# PHY.net
KiCad netlist of a schematic drawn in Altium Designer
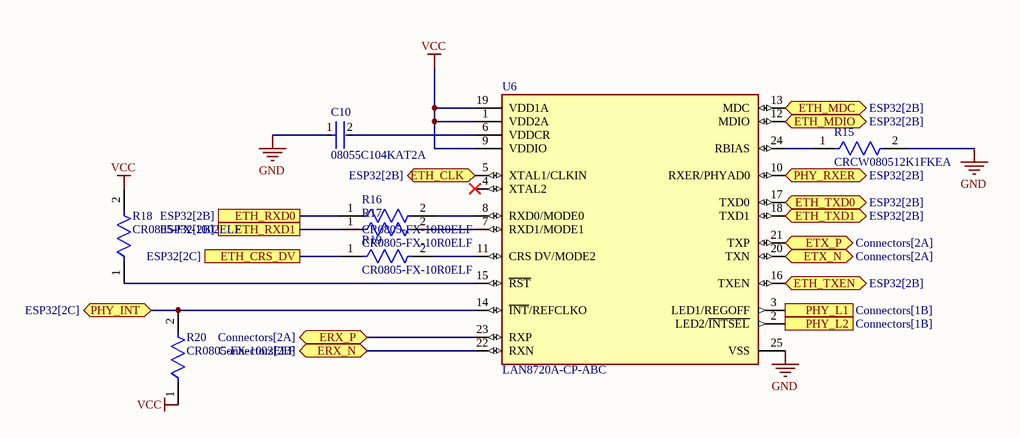
[diagram p0: PHY.SchDoc]

(export (version "E")
  (design (tool "Eeschema 10.0.6"))
  (components
    (comp (ref "C10")
      (value "08055C104KAT2A")
      (footprint "FP-0805-L_2_01_0_2-W_1_25-IPC_C")
      (description "General Purpose Ceramic Capacitor, 0805, 100nF, 10%, X7R, 0.15, 50V")
      (fields (field (name "TOLERANCE") "10%") (field (name "VOLTAGE") "50V"))
      (libsource (lib "Altium Content Vault") (part "02cd4be3c70576c341d710602a673aa"))
    )
    (comp (ref "R15")
      (value "CRCW080512K1FKEA")
      (footprint "FP-CRCW0805-e3-IPC_B")
      (description "RES Thick Film, 12.1kΩ, 1%, 0.125W, 100ppm/°C, 0805")
      (fields (field (name "TOLERANCE") "1%"))
      (libsource (lib "Altium Content Vault") (part "1029c3af85768c4190bb7ad29bc67b5"))
    )
    (comp (ref "R16")
      (value "CR0805-FX-10R0ELF")
      (footprint "FP-CR0805-IPC_B")
      (description "Thick Film Chip Resistors 0805 10Ω 0.125W 1% 100ppm/°C")
      (fields (field (name "TOLERANCE") "1%"))
      (libsource (lib "Altium Content Vault") (part "1029c3af85768c4190bb7ad29bc67b5"))
    )
    (comp (ref "R17")
      (value "CR0805-FX-10R0ELF")
      (footprint "FP-CR0805-IPC_B")
      (description "Thick Film Chip Resistors 0805 10Ω 0.125W 1% 100ppm/°C")
      (fields (field (name "TOLERANCE") "1%"))
      (libsource (lib "Altium Content Vault") (part "1029c3af85768c4190bb7ad29bc67b5"))
    )
    (comp (ref "R18")
      (value "CR0805-FX-1002ELF")
      (footprint "FP-CR0805-IPC_A")
      (description "Thick Film Chip Resistors 0805 10kΩ 0.125W 1% 100ppm/°C")
      (fields (field (name "TOLERANCE") "1%"))
      (libsource (lib "Altium Content Vault") (part "1029c3af85768c4190bb7ad29bc67b5"))
    )
    (comp (ref "R19")
      (value "CR0805-FX-10R0ELF")
      (footprint "FP-CR0805-IPC_B")
      (description "Thick Film Chip Resistors 0805 10Ω 0.125W 1% 100ppm/°C")
      (fields (field (name "TOLERANCE") "1%"))
      (libsource (lib "Altium Content Vault") (part "1029c3af85768c4190bb7ad29bc67b5"))
    )
    (comp (ref "R20")
      (value "CR0805-FX-1002ELF")
      (footprint "FP-CR0805-IPC_A")
      (description "Thick Film Chip Resistors 0805 10kΩ 0.125W 1% 100ppm/°C")
      (fields (field (name "TOLERANCE") "1%"))
      (libsource (lib "Altium Content Vault") (part "1029c3af85768c4190bb7ad29bc67b5"))
    )
    (comp (ref "U6")
      (value "LAN8720A-CP-ABC")
      (footprint "FP-24-S4QFN-4x4B-0_5P-IPC_B")
      (description "IC TRANSCEIVER FULL 2/2 24SQFN")
      (libsource (lib "Altium Content Vault") (part "85d2e6b3fccd3bdbf69e837699e532a"))
    )
  )
  (nets
    (net (code "1") (name "/ERX_N") (class "Default")
      (node (ref "U6") (pin "22") (pinfunction "RXN_22") (pintype "bidirectional"))
    )
    (net (code "2") (name "/ERX_P") (class "Default")
      (node (ref "U6") (pin "23") (pinfunction "RXP_23") (pintype "bidirectional"))
    )
    (net (code "3") (name "/ETH_CLK") (class "Default")
      (node (ref "U6") (pin "5") (pinfunction "XTAL1/CLKIN_5") (pintype "bidirectional"))
    )
    (net (code "4") (name "/ETH_CRS_DV") (class "Default")
      (node (ref "R19") (pin "1") (pinfunction "1_1") (pintype "passive"))
    )
    (net (code "5") (name "/ETH_MDC") (class "Default")
      (node (ref "U6") (pin "13") (pinfunction "MDC_13") (pintype "bidirectional"))
    )
    (net (code "6") (name "/ETH_MDIO") (class "Default")
      (node (ref "U6") (pin "12") (pinfunction "MDIO_12") (pintype "bidirectional"))
    )
    (net (code "7") (name "/ETH_RXD0") (class "Default")
      (node (ref "R16") (pin "1") (pinfunction "1_1") (pintype "passive"))
    )
    (net (code "8") (name "/ETH_RXD1") (class "Default")
      (node (ref "R17") (pin "1") (pinfunction "1_1") (pintype "passive"))
    )
    (net (code "9") (name "/ETH_TXD0") (class "Default")
      (node (ref "U6") (pin "17") (pinfunction "TXD0_17") (pintype "bidirectional"))
    )
    (net (code "10") (name "/ETH_TXD1") (class "Default")
      (node (ref "U6") (pin "18") (pinfunction "TXD1_18") (pintype "bidirectional"))
    )
    (net (code "11") (name "/ETH_TXEN") (class "Default")
      (node (ref "U6") (pin "16") (pinfunction "TXEN_16") (pintype "bidirectional"))
    )
    (net (code "12") (name "/ETX_N") (class "Default")
      (node (ref "U6") (pin "20") (pinfunction "TXN_20") (pintype "bidirectional"))
    )
    (net (code "13") (name "/ETX_P") (class "Default")
      (node (ref "U6") (pin "21") (pinfunction "TXP_21") (pintype "bidirectional"))
    )
    (net (code "14") (name "/PHY_INT") (class "Default")
      (node (ref "R20") (pin "2") (pinfunction "2_2") (pintype "passive"))
      (node (ref "U6") (pin "14") (pinfunction "~{INT}/REFCLKO_14") (pintype "bidirectional"))
    )
    (net (code "15") (name "/PHY_L1") (class "Default")
      (node (ref "U6") (pin "3") (pinfunction "LED1/REGOFF_3") (pintype "output"))
    )
    (net (code "16") (name "/PHY_L2") (class "Default")
      (node (ref "U6") (pin "2") (pinfunction "LED2/~{INTSEL}_2") (pintype "output"))
    )
    (net (code "17") (name "/PHY_RXER") (class "Default")
      (node (ref "U6") (pin "10") (pinfunction "RXER/PHYAD0_10") (pintype "bidirectional"))
    )
    (net (code "18") (name "GND") (class "Default")
      (node (ref "C10") (pin "1") (pinfunction "1_1") (pintype "passive"))
      (node (ref "R15") (pin "2") (pinfunction "2_2") (pintype "passive"))
      (node (ref "U6") (pin "25") (pinfunction "VSS_25") (pintype "power_in"))
    )
    (net (code "19") (name "Net-(U6-CRS_DV{slash}MODE2)") (class "Default")
      (node (ref "R19") (pin "2") (pinfunction "2_2") (pintype "passive"))
      (node (ref "U6") (pin "11") (pinfunction "CRS_DV/MODE2_11") (pintype "bidirectional"))
    )
    (net (code "20") (name "Net-(U6-RBIAS)") (class "Default")
      (node (ref "R15") (pin "1") (pinfunction "1_1") (pintype "passive"))
      (node (ref "U6") (pin "24") (pinfunction "RBIAS_24") (pintype "bidirectional"))
    )
    (net (code "21") (name "Net-(U6-RXD0{slash}MODE0)") (class "Default")
      (node (ref "R16") (pin "2") (pinfunction "2_2") (pintype "passive"))
      (node (ref "U6") (pin "8") (pinfunction "RXD0/MODE0_8") (pintype "bidirectional"))
    )
    (net (code "22") (name "Net-(U6-RXD1{slash}MODE1)") (class "Default")
      (node (ref "R17") (pin "2") (pinfunction "2_2") (pintype "passive"))
      (node (ref "U6") (pin "7") (pinfunction "RXD1/MODE1_7") (pintype "bidirectional"))
    )
    (net (code "23") (name "Net-(U6-VDDCR)") (class "Default")
      (node (ref "C10") (pin "2") (pinfunction "2_2") (pintype "passive"))
      (node (ref "U6") (pin "6") (pinfunction "VDDCR_6") (pintype "power_in"))
    )
    (net (code "24") (name "Net-(U6-~{RST})") (class "Default")
      (node (ref "R18") (pin "1") (pinfunction "1_1") (pintype "passive"))
      (node (ref "U6") (pin "15") (pinfunction "~{RST}_15") (pintype "bidirectional"))
    )
    (net (code "25") (name "VCC") (class "Default")
      (node (ref "R18") (pin "2") (pinfunction "2_2") (pintype "passive"))
      (node (ref "R20") (pin "1") (pinfunction "1_1") (pintype "passive"))
      (node (ref "U6") (pin "1") (pinfunction "VDD2A_1") (pintype "power_in"))
      (node (ref "U6") (pin "19") (pinfunction "VDD1A_19") (pintype "power_in"))
      (node (ref "U6") (pin "9") (pinfunction "VDDIO_9") (pintype "power_in"))
    )
    (net (code "26") (name "unconnected-(U6-XTAL2-Pad4)") (class "Default")
      (node (ref "U6") (pin "4") (pinfunction "XTAL2_4") (pintype "bidirectional+no_connect"))
    )
  )
)
